# butt-on-mk-1_2.net
KiCad netlist of a schematic drawn in EAGLE
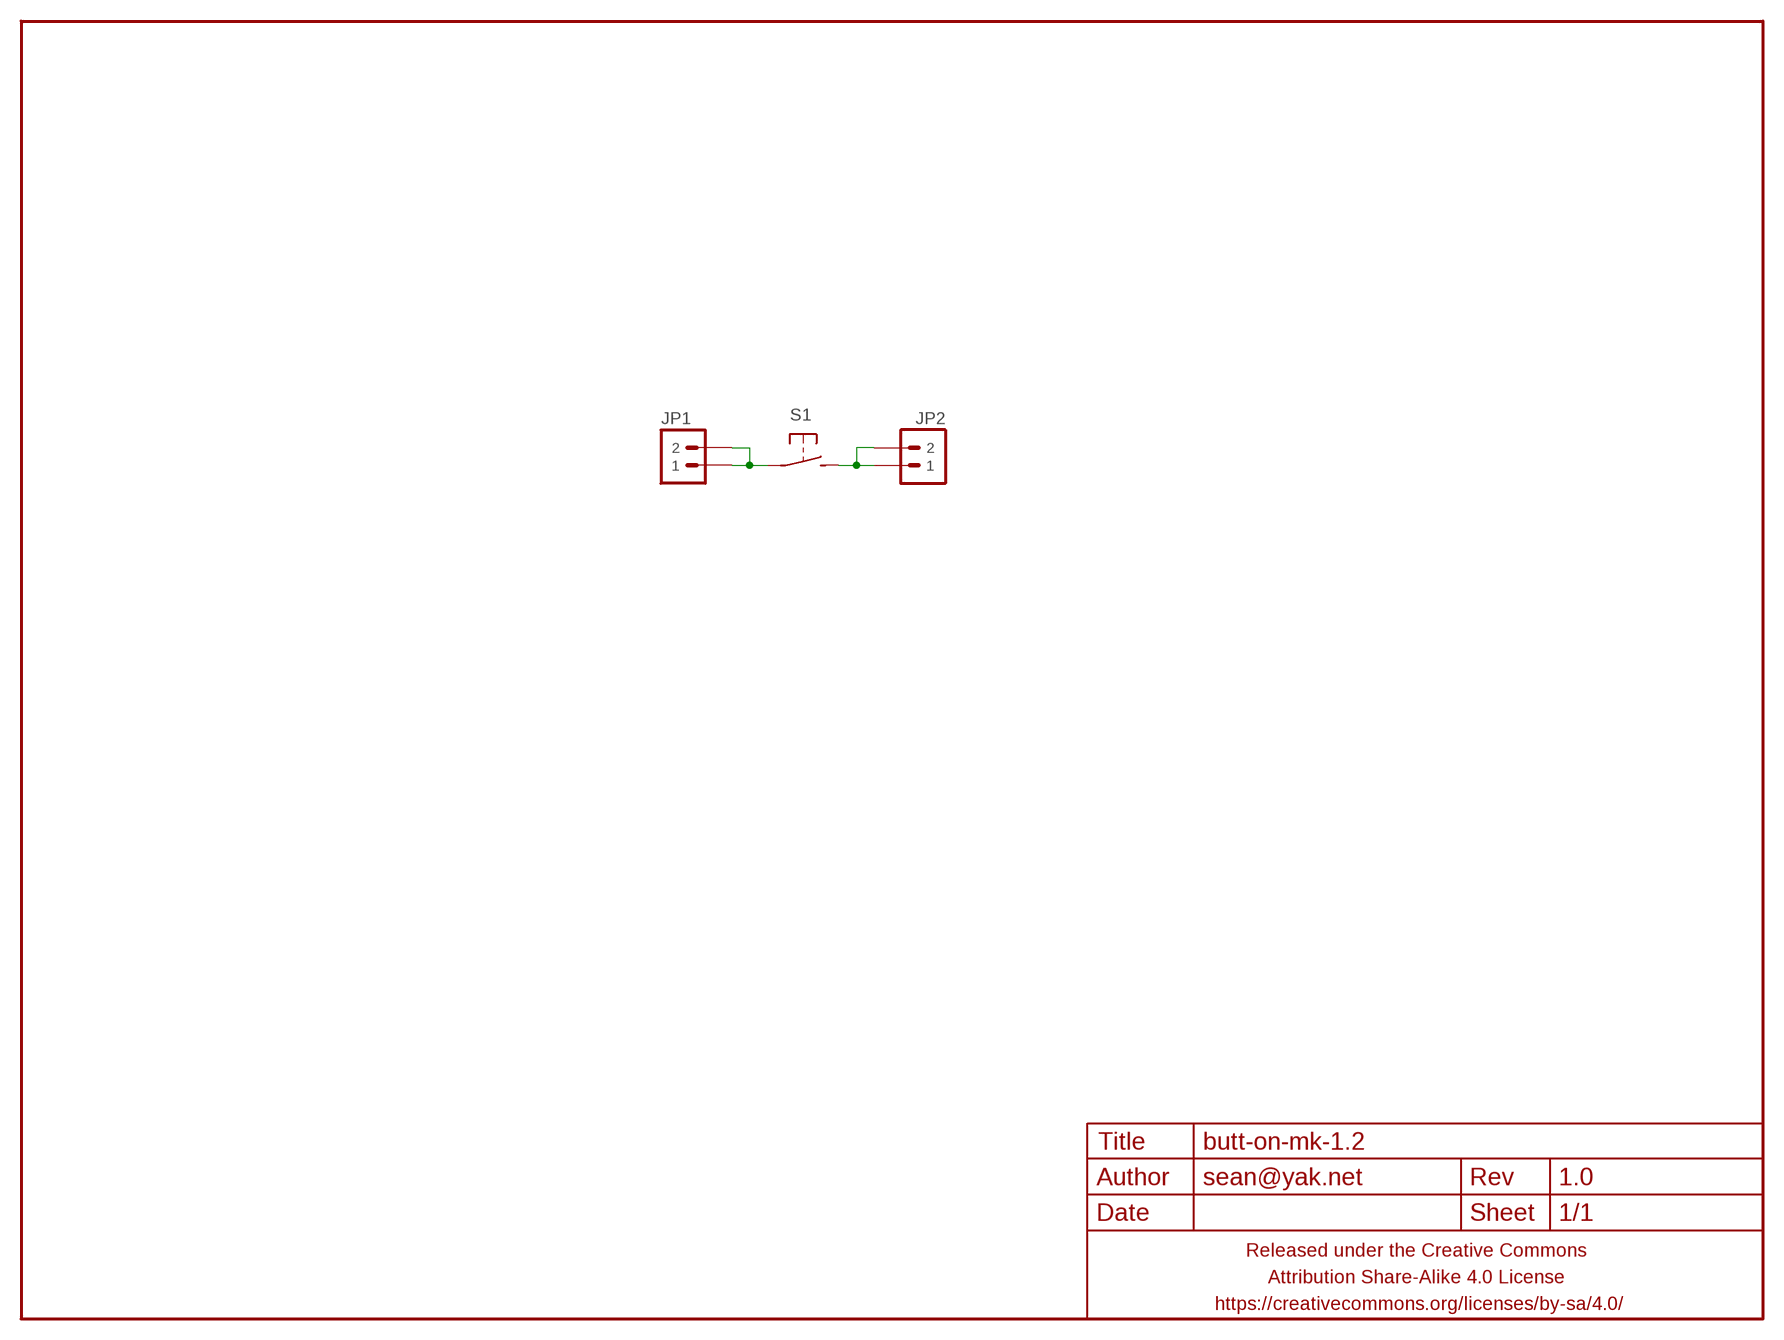
[diagram p0: schematic, sheet 1]

(export (version "E")
  (design (tool "Eeschema 10.0.6"))
  (components
    (comp (ref "FRAME1")
      (value "FRAME-LETTERNO_PACKAGE")
      (footprint "eagle-import:DUMMY")
      (fields (field (name "DESIGNER") "sean@yak.net") (field (name "VERSION") "1.0"))
      (libsource (lib "eagle-import") (part "FRAME-LETTERNO_PACKAGE"))
    )
    (comp (ref "JP1")
      (value "M02PTH-CENTERED")
      (footprint "eagle-import:1X02-CENTER")
      (libsource (lib "eagle-import") (part "M02PTH-CENTERED"))
    )
    (comp (ref "JP2")
      (value "M02PTH-CENTERED")
      (footprint "eagle-import:1X02-CENTER")
      (libsource (lib "eagle-import") (part "M02PTH-CENTERED"))
    )
    (comp (ref "S1")
      (value "SPST-NO-TACT3MM-PTH-SMALL-PADS")
      (footprint "eagle-import:DTS-3-SMALL-PADS")
      (libsource (lib "eagle-import") (part "SPST-NO-TACT3MM-PTH-SMALL-PADS"))
    )
  )
  (nets
    (net (code "1") (name "Net-(JP1-Pad1)") (class "Default")
      (node (ref "JP1") (pin "1") (pinfunction "1_1") (pintype "passive"))
      (node (ref "JP1") (pin "2") (pinfunction "2_2") (pintype "passive"))
      (node (ref "S1") (pin "1") (pinfunction "1_1") (pintype "passive"))
    )
    (net (code "2") (name "Net-(JP2-Pad1)") (class "Default")
      (node (ref "JP2") (pin "1") (pinfunction "1_1") (pintype "passive"))
      (node (ref "JP2") (pin "2") (pinfunction "2_2") (pintype "passive"))
      (node (ref "S1") (pin "2") (pinfunction "2_2") (pintype "passive"))
    )
  )
)
